# visp-i2c-mux-bmp388-eagle-962.net
KiCad netlist of a schematic drawn in EAGLE
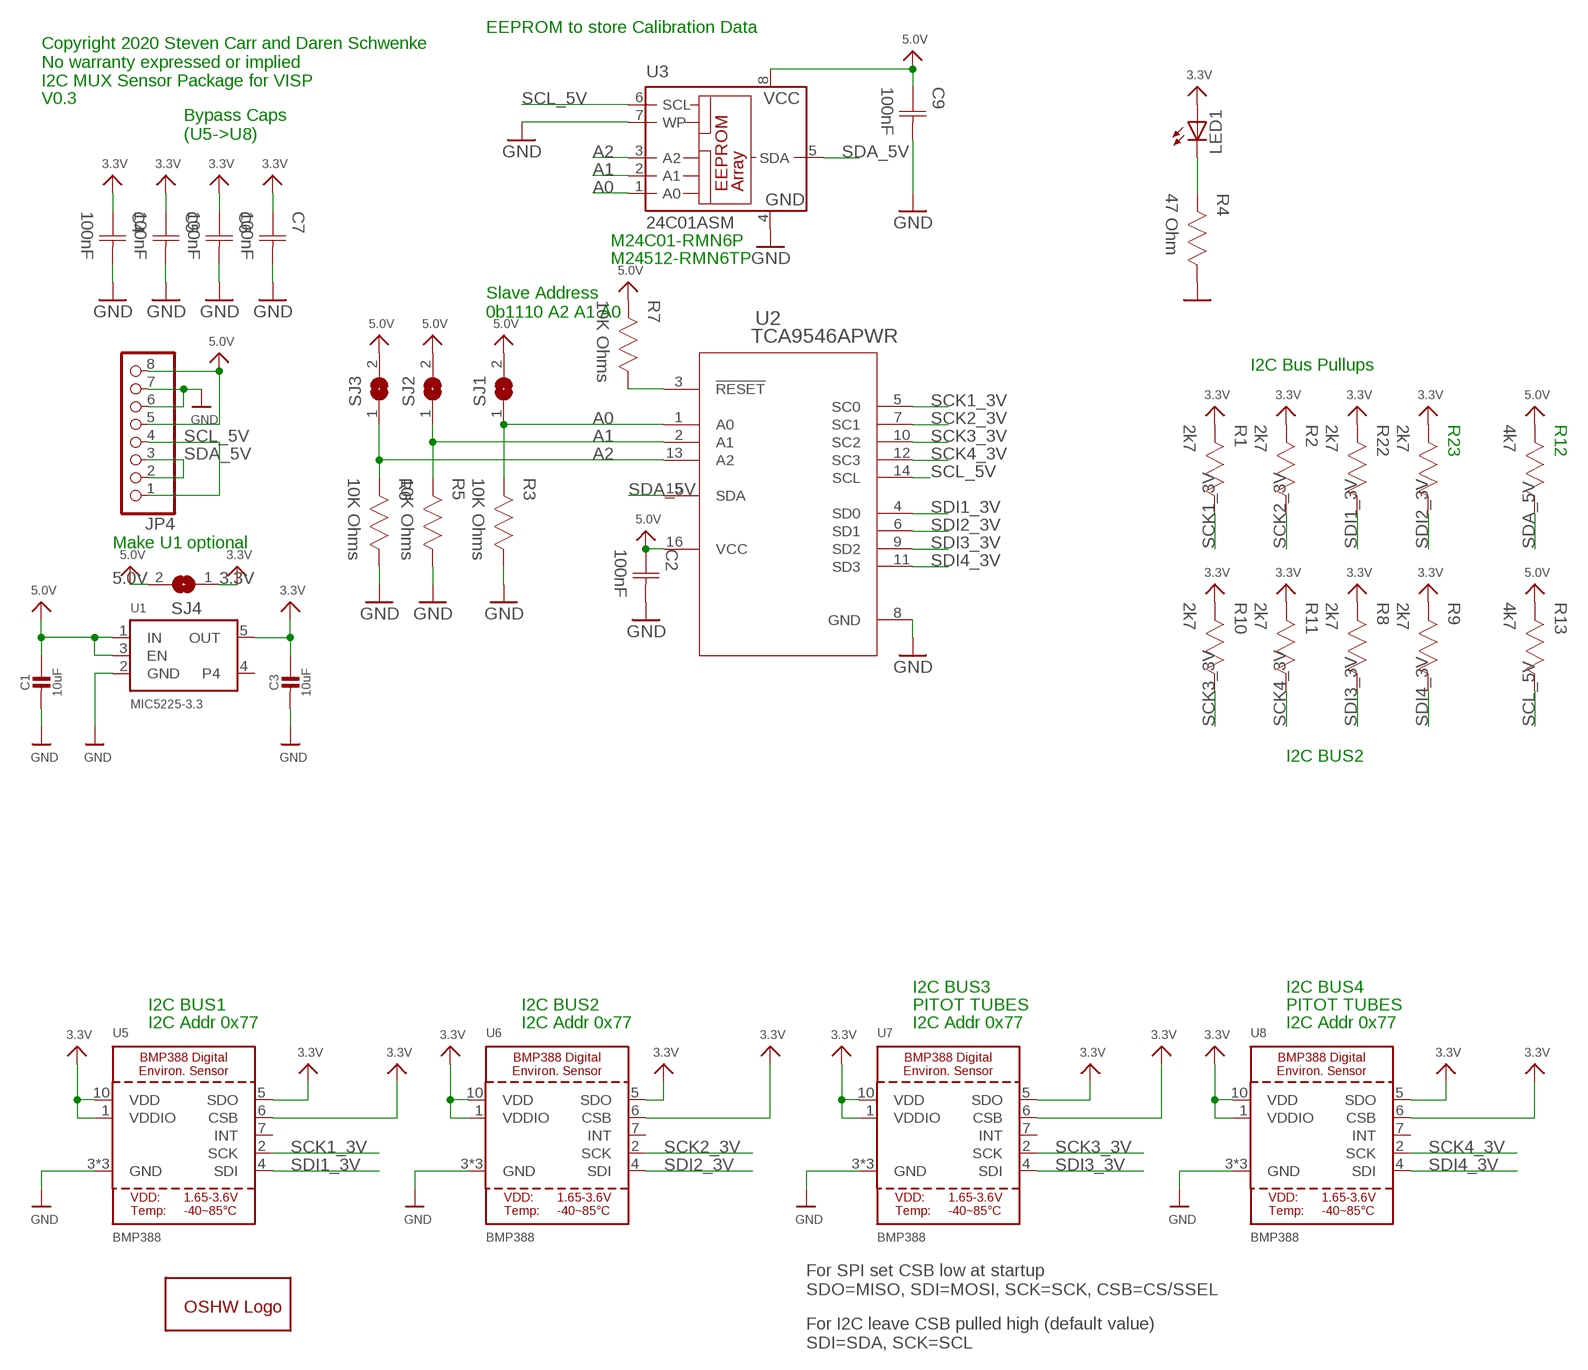
[diagram p0: schematic, sheet 1]

(export (version "E")
  (design (tool "Eeschema 10.0.6"))
  (components
    (comp (ref "C1")
      (value "10uF")
      (footprint "eagle-import:_0805")
      (fields (field (name "MPN") "C1608X5R1A106M080AC"))
      (libsource (lib "eagle-import") (part "CAP_CERAMIC_0805"))
    )
    (comp (ref "C2")
      (value "100nF")
      (footprint "eagle-import:CAP0402")
      (fields (field (name "MPN") "CL10B104KB8NNNC"))
      (libsource (lib "eagle-import") (part "CAPACITOR-0402"))
    )
    (comp (ref "C3")
      (value "10uF")
      (footprint "eagle-import:_0805")
      (fields (field (name "MPN") "C1608X5R1A106M080AC"))
      (libsource (lib "eagle-import") (part "CAP_CERAMIC_0805"))
    )
    (comp (ref "C4")
      (value "100nF")
      (footprint "eagle-import:CAP0402")
      (fields (field (name "MPN") " CL10F104ZO8NNNC "))
      (libsource (lib "eagle-import") (part "CAPACITOR-0402"))
    )
    (comp (ref "C5")
      (value "100nF")
      (footprint "eagle-import:CAP0402")
      (fields (field (name "MPN") " CL10F104ZO8NNNC "))
      (libsource (lib "eagle-import") (part "CAPACITOR-0402"))
    )
    (comp (ref "C6")
      (value "100nF")
      (footprint "eagle-import:CAP0402")
      (fields (field (name "MPN") " CL10F104ZO8NNNC "))
      (libsource (lib "eagle-import") (part "CAPACITOR-0402"))
    )
    (comp (ref "C7")
      (value "100nF")
      (footprint "eagle-import:CAP0402")
      (fields (field (name "MPN") " CL10F104ZO8NNNC "))
      (libsource (lib "eagle-import") (part "CAPACITOR-0402"))
    )
    (comp (ref "C9")
      (value "100nF")
      (footprint "eagle-import:CAP0402")
      (fields (field (name "MPN") "CL10B104KB8NNNC"))
      (libsource (lib "eagle-import") (part "CAPACITOR-0402"))
    )
    (comp (ref "GOLD_ORB_SM1")
      (value "OSHWLOGOLOGO8MM")
      (footprint "eagle-import:OSHW_8MM")
      (libsource (lib "eagle-import") (part "OSHWLOGOLOGO8MM"))
    )
    (comp (ref "JP4")
      (value "PINHD-1X08_2.54")
      (footprint "eagle-import:1X08")
      (libsource (lib "eagle-import") (part "PINHD-1X08_2.54"))
    )
    (comp (ref "LED1")
      (value "LEDCHIP-LED0603")
      (footprint "eagle-import:CHIP-LED0603")
      (fields (field (name "MPN") "SML-D12P8WT86"))
      (libsource (lib "eagle-import") (part "LEDCHIP-LED0603"))
    )
    (comp (ref "R1")
      (value "2k7")
      (footprint "eagle-import:RES0402")
      (fields (field (name "MPN") "CRCW060310K0FKEAC"))
      (libsource (lib "eagle-import") (part "RESISTOR-0402"))
    )
    (comp (ref "R2")
      (value "2k7")
      (footprint "eagle-import:RES0402")
      (fields (field (name "MPN") "CRCW060310K0FKEAC"))
      (libsource (lib "eagle-import") (part "RESISTOR-0402"))
    )
    (comp (ref "R3")
      (value "10K Ohms")
      (footprint "eagle-import:RES0402")
      (fields (field (name "MPN") "CRCW060310K0FKEAC"))
      (libsource (lib "eagle-import") (part "RESISTOR-0402"))
    )
    (comp (ref "R4")
      (value "47 Ohm")
      (footprint "eagle-import:RES0402")
      (fields (field (name "MPN") "RC0603FR-0747RL"))
      (libsource (lib "eagle-import") (part "RESISTOR-0402"))
    )
    (comp (ref "R5")
      (value "10K Ohms")
      (footprint "eagle-import:RES0402")
      (fields (field (name "MPN") "CRCW060310K0FKEAC"))
      (libsource (lib "eagle-import") (part "RESISTOR-0402"))
    )
    (comp (ref "R6")
      (value "10K Ohms")
      (footprint "eagle-import:RES0402")
      (fields (field (name "MPN") "CRCW060310K0FKEAC"))
      (libsource (lib "eagle-import") (part "RESISTOR-0402"))
    )
    (comp (ref "R7")
      (value "10K Ohms")
      (footprint "eagle-import:RES0402")
      (fields (field (name "MPN") "CRCW060310K0FKEAC"))
      (libsource (lib "eagle-import") (part "RESISTOR-0402"))
    )
    (comp (ref "R8")
      (value "2k7")
      (footprint "eagle-import:RES0402")
      (fields (field (name "MPN") "CRCW060310K0FKEAC"))
      (libsource (lib "eagle-import") (part "RESISTOR-0402"))
    )
    (comp (ref "R9")
      (value "2k7")
      (footprint "eagle-import:RES0402")
      (fields (field (name "MPN") "CRCW060310K0FKEAC"))
      (libsource (lib "eagle-import") (part "RESISTOR-0402"))
    )
    (comp (ref "R10")
      (value "2k7")
      (footprint "eagle-import:RES0402")
      (fields (field (name "MPN") "CRCW060310K0FKEAC"))
      (libsource (lib "eagle-import") (part "RESISTOR-0402"))
    )
    (comp (ref "R11")
      (value "2k7")
      (footprint "eagle-import:RES0402")
      (fields (field (name "MPN") "CRCW060310K0FKEAC"))
      (libsource (lib "eagle-import") (part "RESISTOR-0402"))
    )
    (comp (ref "R12")
      (value "4k7")
      (footprint "eagle-import:RES0402")
      (fields (field (name "MPN") "CRCW060310K0FKEAC"))
      (libsource (lib "eagle-import") (part "RESISTOR-0402"))
    )
    (comp (ref "R13")
      (value "4k7")
      (footprint "eagle-import:RES0402")
      (fields (field (name "MPN") "CRCW060310K0FKEAC"))
      (libsource (lib "eagle-import") (part "RESISTOR-0402"))
    )
    (comp (ref "R22")
      (value "2k7")
      (footprint "eagle-import:RES0402")
      (fields (field (name "MPN") "CRCW060310K0FKEAC"))
      (libsource (lib "eagle-import") (part "RESISTOR-0402"))
    )
    (comp (ref "R23")
      (value "2k7")
      (footprint "eagle-import:RES0402")
      (fields (field (name "MPN") "CRCW060310K0FKEAC"))
      (libsource (lib "eagle-import") (part "RESISTOR-0402"))
    )
    (comp (ref "SJ1") (value "SJ") (footprint "eagle-import:SJ") (libsource (lib "eagle-import") (part "SJ")))
    (comp (ref "SJ2") (value "SJ") (footprint "eagle-import:SJ") (libsource (lib "eagle-import") (part "SJ")))
    (comp (ref "SJ3") (value "SJ") (footprint "eagle-import:SJ") (libsource (lib "eagle-import") (part "SJ")))
    (comp (ref "SJ4") (value "SJ") (footprint "eagle-import:SJ") (libsource (lib "eagle-import") (part "SJ")))
    (comp (ref "U1")
      (value "MIC5225-3.3")
      (footprint "eagle-import:SOT23-5")
      (fields (field (name "MPN") "MIC5225-3.3YM5-TR"))
      (libsource (lib "eagle-import") (part "VREG_SOT23-5"))
    )
    (comp (ref "U2")
      (value "TCA9546APWR")
      (footprint "eagle-import:PW16")
      (libsource (lib "eagle-import") (part "TCA9546APWR"))
    )
    (comp (ref "U3")
      (value "24C01ASM")
      (footprint "eagle-import:SO-08M")
      (fields
        (field (name "MF") "MICROCHIP")
        (field (name "MPN") "24C01C/SN")
        (field (name "MPN_1") "M24C01-RMN6P")
      )
      (libsource (lib "eagle-import") (part "24SMC01A"))
    )
    (comp (ref "U5")
      (value "BMP388")
      (footprint "eagle-import:BMP388")
      (libsource (lib "eagle-import") (part "BMP388"))
    )
    (comp (ref "U6")
      (value "BMP388")
      (footprint "eagle-import:BMP388")
      (libsource (lib "eagle-import") (part "BMP388"))
    )
    (comp (ref "U7")
      (value "BMP388")
      (footprint "eagle-import:BMP388")
      (libsource (lib "eagle-import") (part "BMP388"))
    )
    (comp (ref "U8")
      (value "BMP388")
      (footprint "eagle-import:BMP388")
      (libsource (lib "eagle-import") (part "BMP388"))
    )
  )
  (nets
    (net (code "1") (name "/A0") (class "Default")
      (node (ref "R3") (pin "2") (pinfunction "2_2") (pintype "passive"))
      (node (ref "SJ1") (pin "1") (pinfunction "1_1") (pintype "passive"))
      (node (ref "U2") (pin "1") (pinfunction "A0_1") (pintype "input"))
      (node (ref "U3") (pin "1") (pinfunction "A0_1") (pintype "input"))
    )
    (net (code "2") (name "/A1") (class "Default")
      (node (ref "R5") (pin "2") (pinfunction "2_2") (pintype "passive"))
      (node (ref "SJ2") (pin "1") (pinfunction "1_1") (pintype "passive"))
      (node (ref "U2") (pin "2") (pinfunction "A1_2") (pintype "input"))
      (node (ref "U3") (pin "2") (pinfunction "A1_2") (pintype "input"))
    )
    (net (code "3") (name "/A2") (class "Default")
      (node (ref "R6") (pin "2") (pinfunction "2_2") (pintype "passive"))
      (node (ref "SJ3") (pin "1") (pinfunction "1_1") (pintype "passive"))
      (node (ref "U2") (pin "13") (pinfunction "A2_13") (pintype "input"))
      (node (ref "U3") (pin "3") (pinfunction "A2_3") (pintype "input"))
    )
    (net (code "4") (name "/SCK1_3V") (class "Default")
      (node (ref "R1") (pin "1") (pinfunction "1_1") (pintype "passive"))
      (node (ref "U2") (pin "5") (pinfunction "SC0_5") (pintype "passive"))
      (node (ref "U5") (pin "2") (pinfunction "SCK_2") (pintype "input"))
    )
    (net (code "5") (name "/SCK2_3V") (class "Default")
      (node (ref "R2") (pin "1") (pinfunction "1_1") (pintype "passive"))
      (node (ref "U2") (pin "7") (pinfunction "SC1_7") (pintype "passive"))
      (node (ref "U6") (pin "2") (pinfunction "SCK_2") (pintype "input"))
    )
    (net (code "6") (name "/SCK3_3V") (class "Default")
      (node (ref "R10") (pin "1") (pinfunction "1_1") (pintype "passive"))
      (node (ref "U2") (pin "10") (pinfunction "SC2_10") (pintype "passive"))
      (node (ref "U7") (pin "2") (pinfunction "SCK_2") (pintype "input"))
    )
    (net (code "7") (name "/SCK4_3V") (class "Default")
      (node (ref "R11") (pin "1") (pinfunction "1_1") (pintype "passive"))
      (node (ref "U2") (pin "12") (pinfunction "SC3_12") (pintype "passive"))
      (node (ref "U8") (pin "2") (pinfunction "SCK_2") (pintype "input"))
    )
    (net (code "8") (name "/SCL_5V") (class "Default")
      (node (ref "JP4") (pin "1") (pinfunction "1_1") (pintype "passive"))
      (node (ref "JP4") (pin "4") (pinfunction "4_4") (pintype "passive"))
      (node (ref "R13") (pin "1") (pinfunction "1_1") (pintype "passive"))
      (node (ref "U2") (pin "14") (pinfunction "SCL_14") (pintype "passive"))
      (node (ref "U3") (pin "6") (pinfunction "SCL_6") (pintype "input"))
    )
    (net (code "9") (name "/SDA_5V") (class "Default")
      (node (ref "JP4") (pin "2") (pinfunction "2_2") (pintype "passive"))
      (node (ref "JP4") (pin "3") (pinfunction "3_3") (pintype "passive"))
      (node (ref "R12") (pin "1") (pinfunction "1_1") (pintype "passive"))
      (node (ref "U2") (pin "15") (pinfunction "SDA_15") (pintype "passive"))
      (node (ref "U3") (pin "5") (pinfunction "SDA_5") (pintype "bidirectional"))
    )
    (net (code "10") (name "/SDI1_3V") (class "Default")
      (node (ref "R22") (pin "1") (pinfunction "1_1") (pintype "passive"))
      (node (ref "U2") (pin "4") (pinfunction "SD0_4") (pintype "passive"))
      (node (ref "U5") (pin "4") (pinfunction "SDI_4") (pintype "input"))
    )
    (net (code "11") (name "/SDI2_3V") (class "Default")
      (node (ref "R23") (pin "1") (pinfunction "1_1") (pintype "passive"))
      (node (ref "U2") (pin "6") (pinfunction "SD1_6") (pintype "passive"))
      (node (ref "U6") (pin "4") (pinfunction "SDI_4") (pintype "input"))
    )
    (net (code "12") (name "/SDI3_3V") (class "Default")
      (node (ref "R8") (pin "1") (pinfunction "1_1") (pintype "passive"))
      (node (ref "U2") (pin "9") (pinfunction "SD2_9") (pintype "passive"))
      (node (ref "U7") (pin "4") (pinfunction "SDI_4") (pintype "input"))
    )
    (net (code "13") (name "/SDI4_3V") (class "Default")
      (node (ref "R9") (pin "1") (pinfunction "1_1") (pintype "passive"))
      (node (ref "U2") (pin "11") (pinfunction "SD3_11") (pintype "passive"))
      (node (ref "U8") (pin "4") (pinfunction "SDI_4") (pintype "input"))
    )
    (net (code "14") (name "3.3V") (class "Default")
      (node (ref "C3") (pin "1") (pinfunction "1_1") (pintype "passive"))
      (node (ref "C4") (pin "1") (pinfunction "C1_1") (pintype "passive"))
      (node (ref "C5") (pin "1") (pinfunction "C1_1") (pintype "passive"))
      (node (ref "C6") (pin "1") (pinfunction "C1_1") (pintype "passive"))
      (node (ref "C7") (pin "1") (pinfunction "C1_1") (pintype "passive"))
      (node (ref "LED1") (pin "A") (pinfunction "A_A") (pintype "passive"))
      (node (ref "R1") (pin "2") (pinfunction "2_2") (pintype "passive"))
      (node (ref "R10") (pin "2") (pinfunction "2_2") (pintype "passive"))
      (node (ref "R11") (pin "2") (pinfunction "2_2") (pintype "passive"))
      (node (ref "R2") (pin "2") (pinfunction "2_2") (pintype "passive"))
      (node (ref "R22") (pin "2") (pinfunction "2_2") (pintype "passive"))
      (node (ref "R23") (pin "2") (pinfunction "2_2") (pintype "passive"))
      (node (ref "R8") (pin "2") (pinfunction "2_2") (pintype "passive"))
      (node (ref "R9") (pin "2") (pinfunction "2_2") (pintype "passive"))
      (node (ref "SJ4") (pin "1") (pinfunction "1_1") (pintype "passive"))
      (node (ref "U1") (pin "5") (pinfunction "OUT_5") (pintype "power_in"))
      (node (ref "U5") (pin "1") (pinfunction "VDDIO_1") (pintype "power_in"))
      (node (ref "U5") (pin "10") (pinfunction "VDD_10") (pintype "power_in"))
      (node (ref "U5") (pin "5") (pinfunction "SDO_5") (pintype "output"))
      (node (ref "U5") (pin "6") (pinfunction "CSB_6") (pintype "input"))
      (node (ref "U6") (pin "1") (pinfunction "VDDIO_1") (pintype "power_in"))
      (node (ref "U6") (pin "10") (pinfunction "VDD_10") (pintype "power_in"))
      (node (ref "U6") (pin "5") (pinfunction "SDO_5") (pintype "output"))
      (node (ref "U6") (pin "6") (pinfunction "CSB_6") (pintype "input"))
      (node (ref "U7") (pin "1") (pinfunction "VDDIO_1") (pintype "power_in"))
      (node (ref "U7") (pin "10") (pinfunction "VDD_10") (pintype "power_in"))
      (node (ref "U7") (pin "5") (pinfunction "SDO_5") (pintype "output"))
      (node (ref "U7") (pin "6") (pinfunction "CSB_6") (pintype "input"))
      (node (ref "U8") (pin "1") (pinfunction "VDDIO_1") (pintype "power_in"))
      (node (ref "U8") (pin "10") (pinfunction "VDD_10") (pintype "power_in"))
      (node (ref "U8") (pin "5") (pinfunction "SDO_5") (pintype "output"))
      (node (ref "U8") (pin "6") (pinfunction "CSB_6") (pintype "input"))
    )
    (net (code "15") (name "5.0V") (class "Default")
      (node (ref "C1") (pin "1") (pinfunction "1_1") (pintype "passive"))
      (node (ref "C2") (pin "1") (pinfunction "C1_1") (pintype "passive"))
      (node (ref "C9") (pin "1") (pinfunction "C1_1") (pintype "passive"))
      (node (ref "JP4") (pin "5") (pinfunction "5_5") (pintype "passive"))
      (node (ref "JP4") (pin "8") (pinfunction "8_8") (pintype "passive"))
      (node (ref "R12") (pin "2") (pinfunction "2_2") (pintype "passive"))
      (node (ref "R13") (pin "2") (pinfunction "2_2") (pintype "passive"))
      (node (ref "R7") (pin "2") (pinfunction "2_2") (pintype "passive"))
      (node (ref "SJ1") (pin "2") (pinfunction "2_2") (pintype "passive"))
      (node (ref "SJ2") (pin "2") (pinfunction "2_2") (pintype "passive"))
      (node (ref "SJ3") (pin "2") (pinfunction "2_2") (pintype "passive"))
      (node (ref "SJ4") (pin "2") (pinfunction "2_2") (pintype "passive"))
      (node (ref "U1") (pin "1") (pinfunction "IN_1") (pintype "power_in"))
      (node (ref "U1") (pin "3") (pinfunction "EN_3") (pintype "input"))
      (node (ref "U2") (pin "16") (pinfunction "VCC_16") (pintype "power_in"))
      (node (ref "U3") (pin "8") (pinfunction "VCC_8") (pintype "power_in"))
    )
    (net (code "16") (name "GND") (class "Default")
      (node (ref "C1") (pin "2") (pinfunction "2_2") (pintype "passive"))
      (node (ref "C2") (pin "2") (pinfunction "C2_2") (pintype "passive"))
      (node (ref "C3") (pin "2") (pinfunction "2_2") (pintype "passive"))
      (node (ref "C4") (pin "2") (pinfunction "C2_2") (pintype "passive"))
      (node (ref "C5") (pin "2") (pinfunction "C2_2") (pintype "passive"))
      (node (ref "C6") (pin "2") (pinfunction "C2_2") (pintype "passive"))
      (node (ref "C7") (pin "2") (pinfunction "C2_2") (pintype "passive"))
      (node (ref "C9") (pin "2") (pinfunction "C2_2") (pintype "passive"))
      (node (ref "JP4") (pin "6") (pinfunction "6_6") (pintype "passive"))
      (node (ref "JP4") (pin "7") (pinfunction "7_7") (pintype "passive"))
      (node (ref "R3") (pin "1") (pinfunction "1_1") (pintype "passive"))
      (node (ref "R4") (pin "1") (pinfunction "1_1") (pintype "passive"))
      (node (ref "R5") (pin "1") (pinfunction "1_1") (pintype "passive"))
      (node (ref "R6") (pin "1") (pinfunction "1_1") (pintype "passive"))
      (node (ref "U1") (pin "2") (pinfunction "GND_2") (pintype "power_in"))
      (node (ref "U2") (pin "8") (pinfunction "GND_8") (pintype "power_in"))
      (node (ref "U3") (pin "4") (pinfunction "GND_4") (pintype "power_in"))
      (node (ref "U3") (pin "7") (pinfunction "WP_7") (pintype "input"))
      (node (ref "U5") (pin "3") (pinfunction "GND_3") (pintype "power_in"))
      (node (ref "U5") (pin "8") (pinfunction "GND_8") (pintype "power_in"))
      (node (ref "U5") (pin "9") (pinfunction "GND_9") (pintype "power_in"))
      (node (ref "U6") (pin "3") (pinfunction "GND_3") (pintype "power_in"))
      (node (ref "U6") (pin "8") (pinfunction "GND_8") (pintype "power_in"))
      (node (ref "U6") (pin "9") (pinfunction "GND_9") (pintype "power_in"))
      (node (ref "U7") (pin "3") (pinfunction "GND_3") (pintype "power_in"))
      (node (ref "U7") (pin "8") (pinfunction "GND_8") (pintype "power_in"))
      (node (ref "U7") (pin "9") (pinfunction "GND_9") (pintype "power_in"))
      (node (ref "U8") (pin "3") (pinfunction "GND_3") (pintype "power_in"))
      (node (ref "U8") (pin "8") (pinfunction "GND_8") (pintype "power_in"))
      (node (ref "U8") (pin "9") (pinfunction "GND_9") (pintype "power_in"))
    )
    (net (code "17") (name "Net-(LED1-PadC)") (class "Default")
      (node (ref "LED1") (pin "C") (pinfunction "C_C") (pintype "passive"))
      (node (ref "R4") (pin "2") (pinfunction "2_2") (pintype "passive"))
    )
    (net (code "18") (name "Net-(U2-~{RESET})") (class "Default")
      (node (ref "R7") (pin "1") (pinfunction "1_1") (pintype "passive"))
      (node (ref "U2") (pin "3") (pinfunction "~{RESET}_3") (pintype "input"))
    )
    (net (code "19") (name "unconnected-(U1-P4-Pad4)") (class "Default")
      (node (ref "U1") (pin "4") (pinfunction "P4_4") (pintype "bidirectional"))
    )
    (net (code "20") (name "unconnected-(U5-INT-Pad7)") (class "Default")
      (node (ref "U5") (pin "7") (pinfunction "INT_7") (pintype "output"))
    )
    (net (code "21") (name "unconnected-(U6-INT-Pad7)") (class "Default")
      (node (ref "U6") (pin "7") (pinfunction "INT_7") (pintype "output"))
    )
    (net (code "22") (name "unconnected-(U7-INT-Pad7)") (class "Default")
      (node (ref "U7") (pin "7") (pinfunction "INT_7") (pintype "output"))
    )
    (net (code "23") (name "unconnected-(U8-INT-Pad7)") (class "Default")
      (node (ref "U8") (pin "7") (pinfunction "INT_7") (pintype "output"))
    )
  )
)
